# Test_Jig_USB.net
KiCad netlist of a schematic drawn in Altium Designer
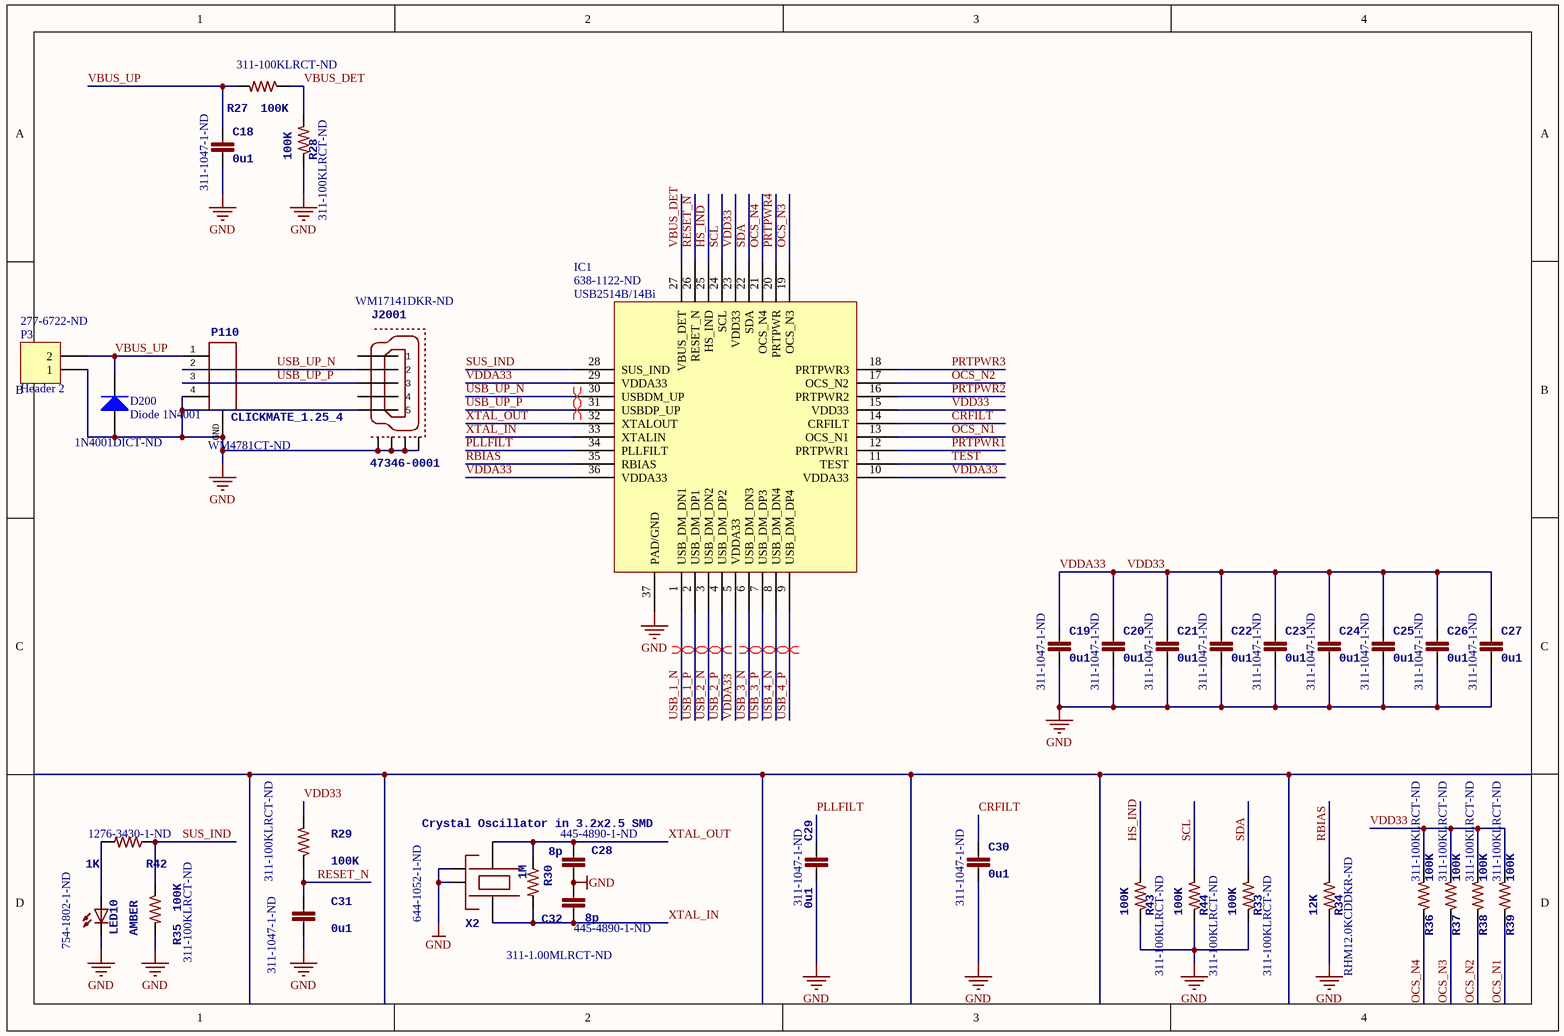
[diagram p0: Test_Jig_USB.SchDoc]

(export (version "E")
  (design (tool "Eeschema 10.0.6"))
  (components
    (comp (ref "C18")
      (value "0u1")
      (footprint "0402-CAP")
      (description "CAP CER 0.1UF 16V Y5V 0402")
      (fields
        (field (name "PARTNO") "CC0402ZRY5V7BB104")
        (field (name "SUPPLIER PART NUMBER 1") "311-1047-1-ND")
        (field (name "3DR_PARTNO") "ECM0700")
      )
      (libsource (lib "pixhawk2") (part "CAP0402"))
    )
    (comp (ref "C19")
      (value "0u1")
      (footprint "0402-CAP")
      (description "CAP CER 0.1UF 16V Y5V 0402")
      (fields
        (field (name "PARTNO") "CC0402ZRY5V7BB104")
        (field (name "SUPPLIER PART NUMBER 1") "311-1047-1-ND")
        (field (name "3DR_PARTNO") "ECM0700")
      )
      (libsource (lib "pixhawk2") (part "CAP0402"))
    )
    (comp (ref "C20")
      (value "0u1")
      (footprint "0402-CAP")
      (description "CAP CER 0.1UF 16V Y5V 0402")
      (fields
        (field (name "PARTNO") "CC0402ZRY5V7BB104")
        (field (name "SUPPLIER PART NUMBER 1") "311-1047-1-ND")
        (field (name "3DR_PARTNO") "ECM0700")
      )
      (libsource (lib "pixhawk2") (part "CAP0402"))
    )
    (comp (ref "C21")
      (value "0u1")
      (footprint "0402-CAP")
      (description "CAP CER 0.1UF 16V Y5V 0402")
      (fields
        (field (name "PARTNO") "CC0402ZRY5V7BB104")
        (field (name "SUPPLIER PART NUMBER 1") "311-1047-1-ND")
        (field (name "3DR_PARTNO") "ECM0700")
      )
      (libsource (lib "pixhawk2") (part "CAP0402"))
    )
    (comp (ref "C22")
      (value "0u1")
      (footprint "0402-CAP")
      (description "CAP CER 0.1UF 16V Y5V 0402")
      (fields
        (field (name "PARTNO") "CC0402ZRY5V7BB104")
        (field (name "SUPPLIER PART NUMBER 1") "311-1047-1-ND")
        (field (name "3DR_PARTNO") "ECM0700")
      )
      (libsource (lib "pixhawk2") (part "CAP0402"))
    )
    (comp (ref "C23")
      (value "0u1")
      (footprint "0402-CAP")
      (description "CAP CER 0.1UF 16V Y5V 0402")
      (fields
        (field (name "PARTNO") "CC0402ZRY5V7BB104")
        (field (name "SUPPLIER PART NUMBER 1") "311-1047-1-ND")
        (field (name "3DR_PARTNO") "ECM0700")
      )
      (libsource (lib "pixhawk2") (part "CAP0402"))
    )
    (comp (ref "C24")
      (value "0u1")
      (footprint "0402-CAP")
      (description "CAP CER 0.1UF 16V Y5V 0402")
      (fields
        (field (name "PARTNO") "CC0402ZRY5V7BB104")
        (field (name "SUPPLIER PART NUMBER 1") "311-1047-1-ND")
        (field (name "3DR_PARTNO") "ECM0700")
      )
      (libsource (lib "pixhawk2") (part "CAP0402"))
    )
    (comp (ref "C25")
      (value "0u1")
      (footprint "0402-CAP")
      (description "CAP CER 0.1UF 16V Y5V 0402")
      (fields
        (field (name "PARTNO") "CC0402ZRY5V7BB104")
        (field (name "SUPPLIER PART NUMBER 1") "311-1047-1-ND")
        (field (name "3DR_PARTNO") "ECM0700")
      )
      (libsource (lib "pixhawk2") (part "CAP0402"))
    )
    (comp (ref "C26")
      (value "0u1")
      (footprint "0402-CAP")
      (description "CAP CER 0.1UF 16V Y5V 0402")
      (fields
        (field (name "PARTNO") "CC0402ZRY5V7BB104")
        (field (name "SUPPLIER PART NUMBER 1") "311-1047-1-ND")
        (field (name "3DR_PARTNO") "ECM0700")
      )
      (libsource (lib "pixhawk2") (part "CAP0402"))
    )
    (comp (ref "C27")
      (value "0u1")
      (footprint "0402-CAP")
      (description "CAP CER 0.1UF 16V Y5V 0402")
      (fields
        (field (name "PARTNO") "CC0402ZRY5V7BB104")
        (field (name "SUPPLIER PART NUMBER 1") "311-1047-1-ND")
        (field (name "3DR_PARTNO") "ECM0700")
      )
      (libsource (lib "pixhawk2") (part "CAP0402"))
    )
    (comp (ref "C28")
      (value "8p")
      (footprint "0402-CAP")
      (description "CAP CER 8PF 50V C0G 0402")
      (fields
        (field (name "PARTNO") "C1005C0G1H080C")
        (field (name "SUPPLIER PART NUMBER 1") "445-4890-1-ND")
        (field (name "3DR_PARTNO") "ECM0710")
      )
      (libsource (lib "") (part "CAP0402_1"))
    )
    (comp (ref "C29")
      (value "0u1")
      (footprint "0402-CAP")
      (description "CAP CER 0.1UF 16V Y5V 0402")
      (fields
        (field (name "PARTNO") "CC0402ZRY5V7BB104")
        (field (name "SUPPLIER PART NUMBER 1") "311-1047-1-ND")
        (field (name "3DR_PARTNO") "ECM0700")
      )
      (libsource (lib "pixhawk2") (part "CAP0402"))
    )
    (comp (ref "C30")
      (value "0u1")
      (footprint "0402-CAP")
      (description "CAP CER 0.1UF 16V Y5V 0402")
      (fields
        (field (name "PARTNO") "CC0402ZRY5V7BB104")
        (field (name "SUPPLIER PART NUMBER 1") "311-1047-1-ND")
        (field (name "3DR_PARTNO") "ECM0700")
      )
      (libsource (lib "pixhawk2") (part "CAP0402"))
    )
    (comp (ref "C31")
      (value "0u1")
      (footprint "0402-CAP")
      (description "CAP CER 0.1UF 16V Y5V 0402")
      (fields
        (field (name "PARTNO") "CC0402ZRY5V7BB104")
        (field (name "SUPPLIER PART NUMBER 1") "311-1047-1-ND")
        (field (name "3DR_PARTNO") "ECM0700")
      )
      (libsource (lib "pixhawk2") (part "CAP0402"))
    )
    (comp (ref "C32")
      (value "8p")
      (footprint "0402-CAP")
      (description "CAP CER 8PF 50V C0G 0402")
      (fields
        (field (name "PARTNO") "C1005C0G1H080C")
        (field (name "SUPPLIER PART NUMBER 1") "445-4890-1-ND")
        (field (name "3DR_PARTNO") "ECM0710")
      )
      (libsource (lib "") (part "CAP0402_1"))
    )
    (comp (ref "D200")
      (value "Diode 1N4001")
      (footprint "DO-41")
      (description "1 Amp General Purpose Rectifier")
      (fields
        (field (name "SUPPLIER PART NUMBER 1") "1N4001DICT-ND")
        (field (name "PUBLISHER") "Altium Limited")
      )
      (libsource (lib "Miscellaneous Devices") (part "Diode 1N4001"))
    )
    (comp (ref "IC1")
      (value "USB2514B/14Bi")
      (footprint "QFN36 USB")
      (fields (field (name "SUPPLIER PART NUMBER 1") "638-1122-ND"))
      (libsource (lib "3DR") (part "USB2514B/14Bi"))
    )
    (comp (ref "J2001")
      (value "47346-0001")
      (footprint "MOLEX-47346-0001")
      (description "MICRO USB B, BOTTOM MOUNT")
      (fields
        (field (name "SUPPLIER PART NUMBER 1") "WM17141DKR-ND")
        (field (name "3DR_PARTNO") "ECM0486")
        (field (name "PARTNO") "0473460001")
      )
      (libsource (lib "pixhawk2") (part "MOLEX-47346-0001"))
    )
    (comp (ref "LED10")
      (value "AMBER")
      (footprint "0603-LED")
      (description "LED 1.6X0.8 DOME ORN CLEAR SMD")
      (fields
        (field (name "PARTNO") "APTD1608SECK")
        (field (name "SUPPLIER PART NUMBER 1") "754-1802-1-ND")
        (field (name "3DR_PARTNO") "ECM0515")
      )
      (libsource (lib "pixhawk2") (part "LED0603"))
    )
    (comp (ref "P3")
      (value "Header 2")
      (footprint "1790283")
      (description "Header, 2-Pin")
      (fields
        (field (name "SUPPLIER PART NUMBER 1") "277-6722-ND")
        (field (name "PUBLISHER") "Altium Limited")
      )
      (libsource (lib "Miscellaneous Connectors") (part "Header 2"))
    )
    (comp (ref "P110")
      (value "CLICKMATE_1.25_4")
      (footprint "CLICKMATE_V4")
      (description "Connector, Rcpt, 4Pos, 1.25MM, W/B, VERT, SMD, Tin")
      (fields (field (name "SUPPLIER PART NUMBER 1") "WM4781CT-ND") (field (name "3DR_PARTNO") "PRT0441"))
      (libsource (lib "PCA_0005_FULL_CB_REV_A") (part "CLICKMATE_1.25_4"))
    )
    (comp (ref "R27")
      (value "100K")
      (footprint "0402-RES")
      (description "RES 100K OHM 1/16W 1% 0402 SMD")
      (fields
        (field (name "SUPPLIER PART NUMBER 1") "311-100KLRCT-ND")
        (field (name "3DR_PARTNO") "ECM0818")
        (field (name "PARTNO") "RC0402FR-07100KL")
      )
      (libsource (lib "pixhawk2") (part "RESISTOR0402-RES"))
    )
    (comp (ref "R28")
      (value "100K")
      (footprint "0402-RES")
      (description "RES 100K OHM 1/16W 1% 0402 SMD")
      (fields
        (field (name "SUPPLIER PART NUMBER 1") "311-100KLRCT-ND")
        (field (name "3DR_PARTNO") "ECM0818")
        (field (name "PARTNO") "RC0402FR-07100KL")
      )
      (libsource (lib "pixhawk2") (part "RESISTOR0402-RES"))
    )
    (comp (ref "R29")
      (value "100K")
      (footprint "0402-RES")
      (description "RES 100K OHM 1/16W 1% 0402 SMD")
      (fields
        (field (name "SUPPLIER PART NUMBER 1") "311-100KLRCT-ND")
        (field (name "3DR_PARTNO") "ECM0818")
        (field (name "PARTNO") "RC0402FR-07100KL")
      )
      (libsource (lib "pixhawk2") (part "RESISTOR0402-RES"))
    )
    (comp (ref "R30")
      (value "1M")
      (footprint "0402-RES")
      (description "RES 1M OHM 1/16W 1% 0402 SMD")
      (fields
        (field (name "PARTNO") "RC0402FR-071ML")
        (field (name "SUPPLIER PART NUMBER 1") "311-1.00MLRCT-ND")
        (field (name "3DR_PARTNO") "ECM0806")
      )
      (libsource (lib "pixhawk2") (part "RESISTOR0402-RES"))
    )
    (comp (ref "R33")
      (value "100K")
      (footprint "0402-RES")
      (description "RES 100K OHM 1/16W 1% 0402 SMD")
      (fields
        (field (name "SUPPLIER PART NUMBER 1") "311-100KLRCT-ND")
        (field (name "3DR_PARTNO") "ECM0818")
        (field (name "PARTNO") "RC0402FR-07100KL")
      )
      (libsource (lib "pixhawk2") (part "RESISTOR0402-RES"))
    )
    (comp (ref "R34")
      (value "12K")
      (footprint "0402-RES")
      (description "RES 12K OHM 1/16W 1% 0402 SMD")
      (fields (field (name "SUPPLIER PART NUMBER 1") "RHM12.0KCDDKR-ND"))
      (libsource (lib "pixhawk2") (part "RESISTOR0402-RES"))
    )
    (comp (ref "R35")
      (value "100K")
      (footprint "0402-RES")
      (description "RES 100K OHM 1/16W 1% 0402 SMD")
      (fields
        (field (name "SUPPLIER PART NUMBER 1") "311-100KLRCT-ND")
        (field (name "3DR_PARTNO") "ECM0818")
        (field (name "PARTNO") "RC0402FR-07100KL")
      )
      (libsource (lib "pixhawk2") (part "RESISTOR0402-RES"))
    )
    (comp (ref "R36")
      (value "100K")
      (footprint "0402-RES")
      (description "RES 100K OHM 1/16W 1% 0402 SMD")
      (fields
        (field (name "SUPPLIER PART NUMBER 1") "311-100KLRCT-ND")
        (field (name "3DR_PARTNO") "ECM0818")
        (field (name "PARTNO") "RC0402FR-07100KL")
      )
      (libsource (lib "pixhawk2") (part "RESISTOR0402-RES"))
    )
    (comp (ref "R37")
      (value "100K")
      (footprint "0402-RES")
      (description "RES 100K OHM 1/16W 1% 0402 SMD")
      (fields
        (field (name "SUPPLIER PART NUMBER 1") "311-100KLRCT-ND")
        (field (name "3DR_PARTNO") "ECM0818")
        (field (name "PARTNO") "RC0402FR-07100KL")
      )
      (libsource (lib "pixhawk2") (part "RESISTOR0402-RES"))
    )
    (comp (ref "R38")
      (value "100K")
      (footprint "0402-RES")
      (description "RES 100K OHM 1/16W 1% 0402 SMD")
      (fields
        (field (name "SUPPLIER PART NUMBER 1") "311-100KLRCT-ND")
        (field (name "3DR_PARTNO") "ECM0818")
        (field (name "PARTNO") "RC0402FR-07100KL")
      )
      (libsource (lib "pixhawk2") (part "RESISTOR0402-RES"))
    )
    (comp (ref "R39")
      (value "100K")
      (footprint "0402-RES")
      (description "RES 100K OHM 1/16W 1% 0402 SMD")
      (fields
        (field (name "SUPPLIER PART NUMBER 1") "311-100KLRCT-ND")
        (field (name "3DR_PARTNO") "ECM0818")
        (field (name "PARTNO") "RC0402FR-07100KL")
      )
      (libsource (lib "pixhawk2") (part "RESISTOR0402-RES"))
    )
    (comp (ref "R42")
      (value "1K")
      (footprint "0402-RES")
      (description "RES 1K OHM 1/16W 1% 0402")
      (fields
        (field (name "PARTNO") "RC1005F102CS")
        (field (name "SUPPLIER PART NUMBER 1") "1276-3430-1-ND")
        (field (name "3DR_PARTNO") "ECM0804")
      )
      (libsource (lib "pixhawk2") (part "RESISTOR0402-RES"))
    )
    (comp (ref "R43")
      (value "100K")
      (footprint "0402-RES")
      (description "RES 100K OHM 1/16W 1% 0402 SMD")
      (fields
        (field (name "SUPPLIER PART NUMBER 1") "311-100KLRCT-ND")
        (field (name "3DR_PARTNO") "ECM0818")
        (field (name "PARTNO") "RC0402FR-07100KL")
      )
      (libsource (lib "pixhawk2") (part "RESISTOR0402-RES"))
    )
    (comp (ref "R44")
      (value "100K")
      (footprint "0402-RES")
      (description "RES 100K OHM 1/16W 1% 0402 SMD")
      (fields
        (field (name "SUPPLIER PART NUMBER 1") "311-100KLRCT-ND")
        (field (name "3DR_PARTNO") "ECM0818")
        (field (name "PARTNO") "RC0402FR-07100KL")
      )
      (libsource (lib "pixhawk2") (part "RESISTOR0402-RES"))
    )
    (comp (ref "X2")
      (value "Crystal Oscillator in 3.2x2.5 SMD")
      (footprint "OSCILLATOR-3.2X2.5")
      (description "CRYSTAL 24MHZ 8PF SMD")
      (fields
        (field (name "SUPPLIER PART NUMBER 1") "644-1052-1-ND")
        (field (name "3DR_PARTNO") "ECM0708")
        (field (name "PARTNO") "NX3225SA-24.000MHZ-STD-CSR-1")
      )
      (libsource (lib "pixhawk2") (part "OSCILLATOR-3.2X2.5"))
    )
  )
  (nets
    (net (code "1") (name "/CRFILT") (class "Default")
      (node (ref "C30") (pin "P$1") (pinfunction "1_P$1") (pintype "passive"))
      (node (ref "IC1") (pin "14") (pinfunction "CRFILT_14") (pintype "passive"))
    )
    (net (code "2") (name "/HS_IND") (class "Default")
      (node (ref "IC1") (pin "25") (pinfunction "HS_IND_25") (pintype "passive"))
      (node (ref "R43") (pin "P$2") (pinfunction "2_P$2") (pintype "passive"))
    )
    (net (code "3") (name "/OCS_N1") (class "Default")
      (node (ref "IC1") (pin "13") (pinfunction "OCS_N1_13") (pintype "passive"))
      (node (ref "R39") (pin "P$1") (pinfunction "1_P$1") (pintype "passive"))
    )
    (net (code "4") (name "/OCS_N2") (class "Default")
      (node (ref "IC1") (pin "17") (pinfunction "OCS_N2_17") (pintype "passive"))
      (node (ref "R38") (pin "P$1") (pinfunction "1_P$1") (pintype "passive"))
    )
    (net (code "5") (name "/OCS_N3") (class "Default")
      (node (ref "IC1") (pin "19") (pinfunction "OCS_N3_19") (pintype "passive"))
      (node (ref "R37") (pin "P$1") (pinfunction "1_P$1") (pintype "passive"))
    )
    (net (code "6") (name "/OCS_N4") (class "Default")
      (node (ref "IC1") (pin "21") (pinfunction "OCS_N4_21") (pintype "passive"))
      (node (ref "R36") (pin "P$1") (pinfunction "1_P$1") (pintype "passive"))
    )
    (net (code "7") (name "/PLLFILT") (class "Default")
      (node (ref "C29") (pin "P$1") (pinfunction "1_P$1") (pintype "passive"))
      (node (ref "IC1") (pin "34") (pinfunction "PLLFILT_34") (pintype "passive"))
    )
    (net (code "8") (name "/PRTPWR1") (class "Default")
      (node (ref "IC1") (pin "12") (pinfunction "PRTPWR1_12") (pintype "passive"))
    )
    (net (code "9") (name "/PRTPWR2") (class "Default")
      (node (ref "IC1") (pin "16") (pinfunction "PRTPWR2_16") (pintype "passive"))
    )
    (net (code "10") (name "/PRTPWR3") (class "Default")
      (node (ref "IC1") (pin "18") (pinfunction "PRTPWR3_18") (pintype "passive"))
    )
    (net (code "11") (name "/PRTPWR4") (class "Default")
      (node (ref "IC1") (pin "20") (pinfunction "PRTPWR_20") (pintype "passive"))
    )
    (net (code "12") (name "/RBIAS") (class "Default")
      (node (ref "IC1") (pin "35") (pinfunction "RBIAS_35") (pintype "passive"))
      (node (ref "R34") (pin "P$2") (pinfunction "2_P$2") (pintype "passive"))
    )
    (net (code "13") (name "/RESET_N") (class "Default")
      (node (ref "C31") (pin "P$1") (pinfunction "1_P$1") (pintype "passive"))
      (node (ref "IC1") (pin "26") (pinfunction "RESET_N_26") (pintype "passive"))
      (node (ref "R29") (pin "P$1") (pinfunction "1_P$1") (pintype "passive"))
    )
    (net (code "14") (name "/SCL") (class "Default")
      (node (ref "IC1") (pin "24") (pinfunction "SCL_24") (pintype "passive"))
      (node (ref "R44") (pin "P$2") (pinfunction "2_P$2") (pintype "passive"))
    )
    (net (code "15") (name "/SDA") (class "Default")
      (node (ref "IC1") (pin "22") (pinfunction "SDA_22") (pintype "passive"))
      (node (ref "R33") (pin "P$2") (pinfunction "2_P$2") (pintype "passive"))
    )
    (net (code "16") (name "/SUS_IND") (class "Default")
      (node (ref "IC1") (pin "28") (pinfunction "SUS_IND_28") (pintype "passive"))
      (node (ref "R35") (pin "P$1") (pinfunction "1_P$1") (pintype "passive"))
      (node (ref "R42") (pin "P$1") (pinfunction "1_P$1") (pintype "passive"))
    )
    (net (code "17") (name "/TEST") (class "Default")
      (node (ref "IC1") (pin "11") (pinfunction "TEST_11") (pintype "passive"))
    )
    (net (code "18") (name "/USB_1_N") (class "Default")
      (node (ref "IC1") (pin "1") (pinfunction "USB_DM_DN1_1") (pintype "passive"))
    )
    (net (code "19") (name "/USB_1_P") (class "Default")
      (node (ref "IC1") (pin "2") (pinfunction "USB_DM_DP1_2") (pintype "passive"))
    )
    (net (code "20") (name "/USB_2_N") (class "Default")
      (node (ref "IC1") (pin "3") (pinfunction "USB_DM_DN2_3") (pintype "passive"))
    )
    (net (code "21") (name "/USB_2_P") (class "Default")
      (node (ref "IC1") (pin "4") (pinfunction "USB_DM_DP2_4") (pintype "passive"))
    )
    (net (code "22") (name "/USB_3_N") (class "Default")
      (node (ref "IC1") (pin "6") (pinfunction "USB_DM_DN3_6") (pintype "passive"))
    )
    (net (code "23") (name "/USB_3_P") (class "Default")
      (node (ref "IC1") (pin "7") (pinfunction "USB_DM_DP3_7") (pintype "passive"))
    )
    (net (code "24") (name "/USB_4_N") (class "Default")
      (node (ref "IC1") (pin "8") (pinfunction "USB_DM_DN4_8") (pintype "passive"))
    )
    (net (code "25") (name "/USB_4_P") (class "Default")
      (node (ref "IC1") (pin "9") (pinfunction "USB_DM_DP4_9") (pintype "passive"))
    )
    (net (code "26") (name "/USB_UP_N") (class "Default")
      (node (ref "IC1") (pin "30") (pinfunction "USBDM_UP_30") (pintype "passive"))
      (node (ref "J2001") (pin "D-") (pinfunction "2_D-") (pintype "passive"))
      (node (ref "P110") (pin "2") (pinfunction "2_2") (pintype "passive"))
    )
    (net (code "27") (name "/USB_UP_P") (class "Default")
      (node (ref "IC1") (pin "31") (pinfunction "USBDP_UP_31") (pintype "passive"))
      (node (ref "J2001") (pin "D+") (pinfunction "3_D+") (pintype "passive"))
      (node (ref "P110") (pin "3") (pinfunction "3_3") (pintype "passive"))
    )
    (net (code "28") (name "/VBUS_DET") (class "Default")
      (node (ref "IC1") (pin "27") (pinfunction "VBUS_DET_27") (pintype "passive"))
      (node (ref "R27") (pin "P$1") (pinfunction "1_P$1") (pintype "passive"))
      (node (ref "R28") (pin "P$2") (pinfunction "2_P$2") (pintype "passive"))
    )
    (net (code "29") (name "/VBUS_UP") (class "Default")
      (node (ref "C18") (pin "P$1") (pinfunction "1_P$1") (pintype "passive"))
      (node (ref "D200") (pin "2") (pinfunction "K_2") (pintype "passive"))
      (node (ref "P110") (pin "1") (pinfunction "1_1") (pintype "passive"))
      (node (ref "P3") (pin "2") (pinfunction "2_2") (pintype "passive"))
      (node (ref "R27") (pin "P$2") (pinfunction "2_P$2") (pintype "passive"))
    )
    (net (code "30") (name "/VDD33") (class "Default")
      (node (ref "C19") (pin "P$1") (pinfunction "1_P$1") (pintype "passive"))
      (node (ref "C20") (pin "P$1") (pinfunction "1_P$1") (pintype "passive"))
      (node (ref "C21") (pin "P$1") (pinfunction "1_P$1") (pintype "passive"))
      (node (ref "C22") (pin "P$1") (pinfunction "1_P$1") (pintype "passive"))
      (node (ref "C23") (pin "P$1") (pinfunction "1_P$1") (pintype "passive"))
      (node (ref "C24") (pin "P$1") (pinfunction "1_P$1") (pintype "passive"))
      (node (ref "C25") (pin "P$1") (pinfunction "1_P$1") (pintype "passive"))
      (node (ref "C26") (pin "P$1") (pinfunction "1_P$1") (pintype "passive"))
      (node (ref "C27") (pin "P$1") (pinfunction "1_P$1") (pintype "passive"))
      (node (ref "IC1") (pin "10") (pinfunction "VDDA33_10") (pintype "passive"))
      (node (ref "IC1") (pin "15") (pinfunction "VDD33_15") (pintype "passive"))
      (node (ref "IC1") (pin "23") (pinfunction "VDD33_23") (pintype "passive"))
      (node (ref "IC1") (pin "29") (pinfunction "VDDA33_29") (pintype "passive"))
      (node (ref "IC1") (pin "36") (pinfunction "VDDA33_36") (pintype "passive"))
      (node (ref "IC1") (pin "5") (pinfunction "VDDA33_5") (pintype "passive"))
      (node (ref "R29") (pin "P$2") (pinfunction "2_P$2") (pintype "passive"))
      (node (ref "R36") (pin "P$2") (pinfunction "2_P$2") (pintype "passive"))
      (node (ref "R37") (pin "P$2") (pinfunction "2_P$2") (pintype "passive"))
      (node (ref "R38") (pin "P$2") (pinfunction "2_P$2") (pintype "passive"))
      (node (ref "R39") (pin "P$2") (pinfunction "2_P$2") (pintype "passive"))
    )
    (net (code "31") (name "/XTAL_IN") (class "Default")
      (node (ref "C32") (pin "P$1") (pinfunction "1_P$1") (pintype "passive"))
      (node (ref "IC1") (pin "33") (pinfunction "XTALIN_33") (pintype "passive"))
      (node (ref "R30") (pin "P$2") (pinfunction "2_P$2") (pintype "passive"))
      (node (ref "X2") (pin "3") (pinfunction "3_3") (pintype "passive"))
    )
    (net (code "32") (name "/XTAL_OUT") (class "Default")
      (node (ref "C28") (pin "P$2") (pinfunction "2_P$2") (pintype "passive"))
      (node (ref "IC1") (pin "32") (pinfunction "XTALOUT_32") (pintype "passive"))
      (node (ref "R30") (pin "P$1") (pinfunction "1_P$1") (pintype "passive"))
      (node (ref "X2") (pin "1") (pinfunction "1_1") (pintype "passive"))
    )
    (net (code "33") (name "GND") (class "Default")
      (node (ref "C18") (pin "P$2") (pinfunction "2_P$2") (pintype "passive"))
      (node (ref "C19") (pin "P$2") (pinfunction "2_P$2") (pintype "passive"))
      (node (ref "C20") (pin "P$2") (pinfunction "2_P$2") (pintype "passive"))
      (node (ref "C21") (pin "P$2") (pinfunction "2_P$2") (pintype "passive"))
      (node (ref "C22") (pin "P$2") (pinfunction "2_P$2") (pintype "passive"))
      (node (ref "C23") (pin "P$2") (pinfunction "2_P$2") (pintype "passive"))
      (node (ref "C24") (pin "P$2") (pinfunction "2_P$2") (pintype "passive"))
      (node (ref "C25") (pin "P$2") (pinfunction "2_P$2") (pintype "passive"))
      (node (ref "C26") (pin "P$2") (pinfunction "2_P$2") (pintype "passive"))
      (node (ref "C27") (pin "P$2") (pinfunction "2_P$2") (pintype "passive"))
      (node (ref "C28") (pin "P$1") (pinfunction "1_P$1") (pintype "passive"))
      (node (ref "C29") (pin "P$2") (pinfunction "2_P$2") (pintype "passive"))
      (node (ref "C30") (pin "P$2") (pinfunction "2_P$2") (pintype "passive"))
      (node (ref "C31") (pin "P$2") (pinfunction "2_P$2") (pintype "passive"))
      (node (ref "C32") (pin "P$2") (pinfunction "2_P$2") (pintype "passive"))
      (node (ref "D200") (pin "1") (pinfunction "A_1") (pintype "passive"))
      (node (ref "IC1") (pin "37") (pinfunction "PAD/GND_37") (pintype "passive"))
      (node (ref "J2001") (pin "GND") (pinfunction "5_GND") (pintype "open_emitter"))
      (node (ref "J2001") (pin "GND1") (pinfunction "GND1_GND1") (pintype "passive"))
      (node (ref "J2001") (pin "GND2") (pinfunction "GND2_GND2") (pintype "passive"))
      (node (ref "J2001") (pin "GND3") (pinfunction "GND3_GND3") (pintype "passive"))
      (node (ref "J2001") (pin "GND4") (pinfunction "GND4_GND4") (pintype "passive"))
      (node (ref "LED10") (pin "C") (pinfunction "C_C") (pintype "passive"))
      (node (ref "P110") (pin "4") (pinfunction "4_4") (pintype "passive"))
      (node (ref "P110") (pin "GND") (pinfunction "GND_GND") (pintype "passive"))
      (node (ref "P3") (pin "1") (pinfunction "1_1") (pintype "passive"))
      (node (ref "R28") (pin "P$1") (pinfunction "1_P$1") (pintype "passive"))
      (node (ref "R33") (pin "P$1") (pinfunction "1_P$1") (pintype "passive"))
      (node (ref "R34") (pin "P$1") (pinfunction "1_P$1") (pintype "passive"))
      (node (ref "R35") (pin "P$2") (pinfunction "2_P$2") (pintype "passive"))
      (node (ref "R43") (pin "P$1") (pinfunction "1_P$1") (pintype "passive"))
      (node (ref "R44") (pin "P$1") (pinfunction "1_P$1") (pintype "passive"))
      (node (ref "X2") (pin "2") (pinfunction "NC_2_2") (pintype "open_emitter"))
      (node (ref "X2") (pin "4") (pinfunction "NC_4_4") (pintype "open_emitter"))
    )
    (net (code "34") (name "Net-(R42-2)") (class "Default")
      (node (ref "LED10") (pin "A") (pinfunction "A_A") (pintype "passive"))
      (node (ref "R42") (pin "P$2") (pinfunction "2_P$2") (pintype "passive"))
    )
    (net (code "35") (name "unconnected-(J2001-1-PadVBUS)") (class "Default")
      (node (ref "J2001") (pin "VBUS") (pinfunction "1_VBUS") (pintype "open_emitter"))
    )
    (net (code "36") (name "unconnected-(J2001-4-PadID)") (class "Default")
      (node (ref "J2001") (pin "ID") (pinfunction "4_ID") (pintype "passive"))
    )
  )
)
